# Adafruit_CLUE_nRF52840_Express.net
KiCad netlist of a schematic drawn in EAGLE
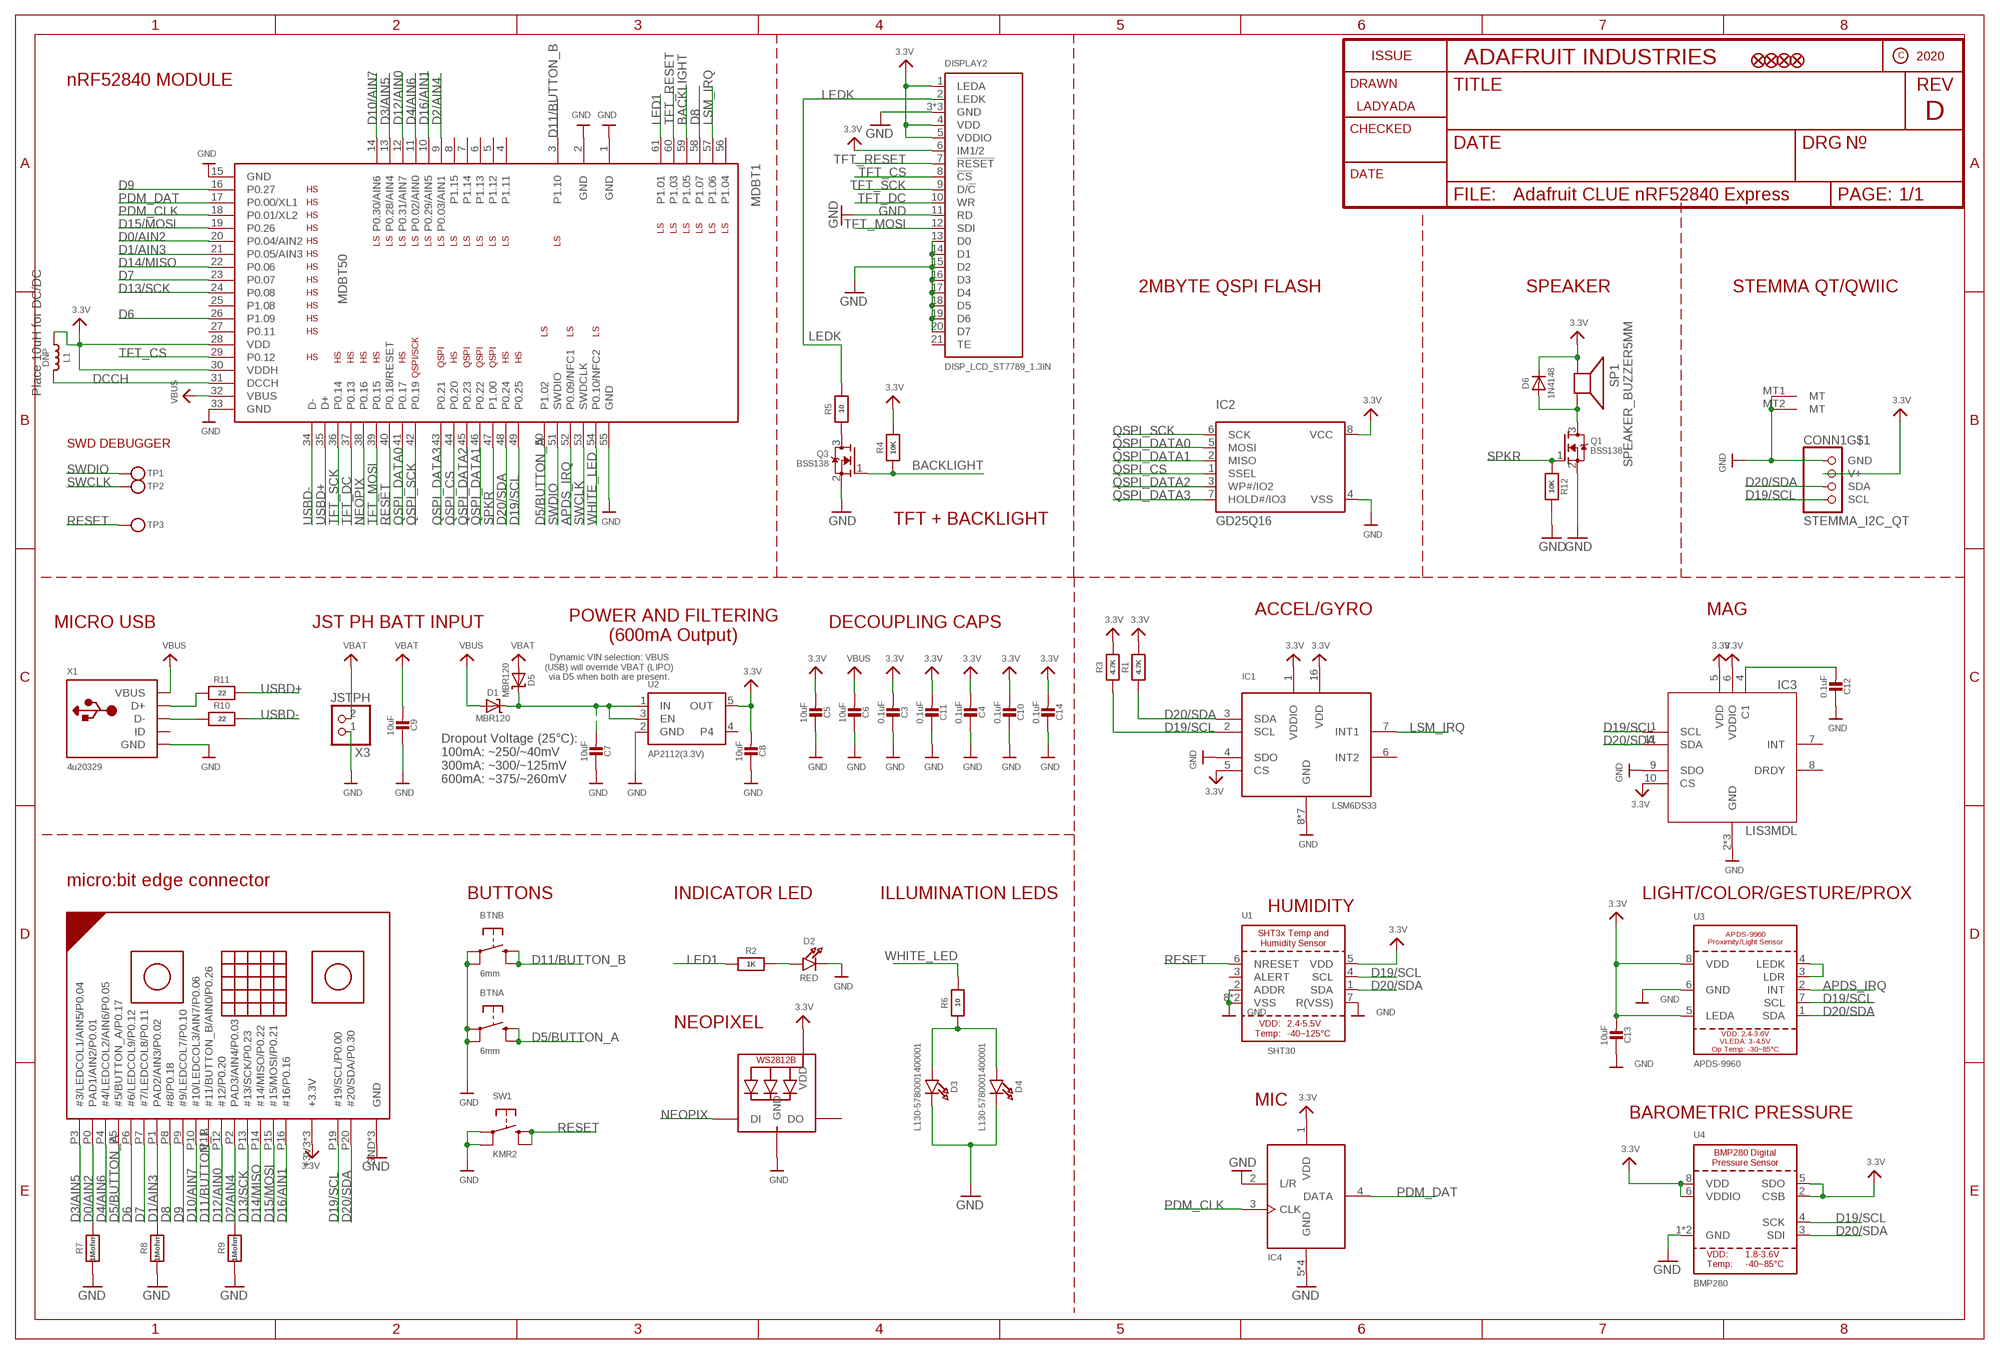
[diagram p0: schematic, sheet 1]

(export (version "E")
  (design (tool "Eeschema 10.0.6"))
  (components
    (comp (ref "BTNA")
      (value "6mm")
      (footprint "eagle-import:6MMX6MM_TACTILE_SMT")
      (libsource (lib "eagle-import") (part "SWITCH_TACT_SMT_6MM"))
    )
    (comp (ref "BTNB")
      (value "6mm")
      (footprint "eagle-import:6MMX6MM_TACTILE_SMT")
      (libsource (lib "eagle-import") (part "SWITCH_TACT_SMT_6MM"))
    )
    (comp (ref "C3")
      (value "0.1uF")
      (footprint "eagle-import:0603-NO")
      (libsource (lib "eagle-import") (part "CAP_CERAMIC0603_NO"))
    )
    (comp (ref "C4")
      (value "0.1uF")
      (footprint "eagle-import:0603-NO")
      (libsource (lib "eagle-import") (part "CAP_CERAMIC0603_NO"))
    )
    (comp (ref "C5")
      (value "10uF")
      (footprint "eagle-import:0805-NO")
      (libsource (lib "eagle-import") (part "CAP_CERAMIC0805-NOOUTLINE"))
    )
    (comp (ref "C6")
      (value "10uF")
      (footprint "eagle-import:0805-NO")
      (libsource (lib "eagle-import") (part "CAP_CERAMIC0805-NOOUTLINE"))
    )
    (comp (ref "C7")
      (value "10uF")
      (footprint "eagle-import:0805-NO")
      (libsource (lib "eagle-import") (part "CAP_CERAMIC0805-NOOUTLINE"))
    )
    (comp (ref "C8")
      (value "10uF")
      (footprint "eagle-import:0805-NO")
      (libsource (lib "eagle-import") (part "CAP_CERAMIC0805-NOOUTLINE"))
    )
    (comp (ref "C9")
      (value "10uF")
      (footprint "eagle-import:0805-NO")
      (libsource (lib "eagle-import") (part "CAP_CERAMIC0805-NOOUTLINE"))
    )
    (comp (ref "C10")
      (value "0.1uF")
      (footprint "eagle-import:0603-NO")
      (libsource (lib "eagle-import") (part "CAP_CERAMIC0603_NO"))
    )
    (comp (ref "C11")
      (value "0.1uF")
      (footprint "eagle-import:0603-NO")
      (libsource (lib "eagle-import") (part "CAP_CERAMIC0603_NO"))
    )
    (comp (ref "C12")
      (value "0.1uF")
      (footprint "eagle-import:0603-NO")
      (libsource (lib "eagle-import") (part "CAP_CERAMIC0603_NO"))
    )
    (comp (ref "C13")
      (value "10uF")
      (footprint "eagle-import:0805-NO")
      (libsource (lib "eagle-import") (part "CAP_CERAMIC0805-NOOUTLINE"))
    )
    (comp (ref "C14")
      (value "0.1uF")
      (footprint "eagle-import:0603-NO")
      (libsource (lib "eagle-import") (part "CAP_CERAMIC0603_NO"))
    )
    (comp (ref "CONN1")
      (value "STEMMA_I2C_QT")
      (footprint "eagle-import:JST_SH4")
      (libsource (lib "eagle-import") (part "STEMMA_I2C_QT"))
    )
    (comp (ref "D1")
      (value "MBR120")
      (footprint "eagle-import:SOD-123")
      (libsource (lib "eagle-import") (part "DIODE-SCHOTTKYSOD-123"))
    )
    (comp (ref "D2")
      (value "RED")
      (footprint "eagle-import:CHIPLED_0603_NOOUTLINE")
      (libsource (lib "eagle-import") (part "LED0603_NOOUTLINE"))
    )
    (comp (ref "D3")
      (value "L130-5780001400001")
      (footprint "eagle-import:EVERLIGHT_45-21")
      (libsource (lib "eagle-import") (part "LEDEV45-21"))
    )
    (comp (ref "D4")
      (value "L130-5780001400001")
      (footprint "eagle-import:EVERLIGHT_45-21")
      (libsource (lib "eagle-import") (part "LEDEV45-21"))
    )
    (comp (ref "D5")
      (value "MBR120")
      (footprint "eagle-import:SOD-123")
      (libsource (lib "eagle-import") (part "DIODE-SCHOTTKYSOD-123"))
    )
    (comp (ref "D6")
      (value "1N4148")
      (footprint "eagle-import:SOD-323")
      (libsource (lib "eagle-import") (part "DIODESOD-323"))
    )
    (comp (ref "DISPLAY2")
      (value "DISP_LCD_ST7789_1.3IN")
      (footprint "eagle-import:TFT_1.3IN_240X240_24P")
      (libsource (lib "eagle-import") (part "DISP_LCD_ST7789_1.3IN"))
    )
    (comp (ref "FID1")
      (value "FIDUCIAL_1MM")
      (footprint "eagle-import:FIDUCIAL_1MM")
      (libsource (lib "eagle-import") (part "FIDUCIAL_1MM"))
    )
    (comp (ref "FID2")
      (value "FIDUCIAL_1MM")
      (footprint "eagle-import:FIDUCIAL_1MM")
      (libsource (lib "eagle-import") (part "FIDUCIAL_1MM"))
    )
    (comp (ref "FID3")
      (value "FIDUCIAL_1MM")
      (footprint "eagle-import:FIDUCIAL_1MM")
      (libsource (lib "eagle-import") (part "FIDUCIAL_1MM"))
    )
    (comp (ref "FID4")
      (value "FIDUCIAL_1MM")
      (footprint "eagle-import:FIDUCIAL_1MM")
      (libsource (lib "eagle-import") (part "FIDUCIAL_1MM"))
    )
    (comp (ref "IC1")
      (value "LSM6DS33")
      (footprint "eagle-import:LGA16_3X3MM")
      (libsource (lib "eagle-import") (part "LSM6DS33"))
    )
    (comp (ref "IC2")
      (value "GD25Q16")
      (footprint "eagle-import:SOIC8_150MIL")
      (libsource (lib "eagle-import") (part "SPIFLASH_8PIN"))
    )
    (comp (ref "IC3")
      (value "LIS3MDL")
      (footprint "eagle-import:LGA12_2X2MM")
      (libsource (lib "eagle-import") (part "LIS3MDL"))
    )
    (comp (ref "IC4")
      (value "MIC_PDM")
      (footprint "eagle-import:SPK0415HM4H")
      (libsource (lib "eagle-import") (part "MIC_PDM_SPK0415"))
    )
    (comp (ref "L1")
      (value "DNP")
      (footprint "eagle-import:_0805MP")
      (libsource (lib "eagle-import") (part "INDUCTOR_0805MP"))
    )
    (comp (ref "LED1")
      (value "WS2812B3535")
      (footprint "eagle-import:LED3535")
      (libsource (lib "eagle-import") (part "WS2812B3535"))
    )
    (comp (ref "MB1")
      (value "MICRO:BIT_EDGE")
      (footprint "eagle-import:MICROBIT_EDGE")
      (libsource (lib "eagle-import") (part "MICRO{colon}BIT_EDGE"))
    )
    (comp (ref "MDBT1")
      (value "MDBT50")
      (footprint "eagle-import:MDBT50")
      (libsource (lib "eagle-import") (part "MDBT50"))
    )
    (comp (ref "Q1")
      (value "BSS138")
      (footprint "eagle-import:SOT23-WIDE")
      (libsource (lib "eagle-import") (part "MOSFET-NWIDE"))
    )
    (comp (ref "Q3")
      (value "BSS138")
      (footprint "eagle-import:SOT23-WIDE")
      (libsource (lib "eagle-import") (part "MOSFET-NWIDE"))
    )
    (comp (ref "R1")
      (value "4.7K")
      (footprint "eagle-import:0603-NO")
      (libsource (lib "eagle-import") (part "RESISTOR_0603_NOOUT"))
    )
    (comp (ref "R2")
      (value "1K")
      (footprint "eagle-import:0603-NO")
      (libsource (lib "eagle-import") (part "RESISTOR_0603_NOOUT"))
    )
    (comp (ref "R3")
      (value "4.7K")
      (footprint "eagle-import:0603-NO")
      (libsource (lib "eagle-import") (part "RESISTOR_0603_NOOUT"))
    )
    (comp (ref "R4")
      (value "10K")
      (footprint "eagle-import:0603-NO")
      (libsource (lib "eagle-import") (part "RESISTOR_0603_NOOUT"))
    )
    (comp (ref "R5")
      (value "10")
      (footprint "eagle-import:0603-NO")
      (libsource (lib "eagle-import") (part "RESISTOR_0603_NOOUT"))
    )
    (comp (ref "R6")
      (value "10")
      (footprint "eagle-import:0603-NO")
      (libsource (lib "eagle-import") (part "RESISTOR_0603_NOOUT"))
    )
    (comp (ref "R7")
      (value "1Mohm")
      (footprint "eagle-import:0603-NO")
      (libsource (lib "eagle-import") (part "RESISTOR_0603_NOOUT"))
    )
    (comp (ref "R8")
      (value "1Mohm")
      (footprint "eagle-import:0603-NO")
      (libsource (lib "eagle-import") (part "RESISTOR_0603_NOOUT"))
    )
    (comp (ref "R9")
      (value "1Mohm")
      (footprint "eagle-import:0603-NO")
      (libsource (lib "eagle-import") (part "RESISTOR_0603_NOOUT"))
    )
    (comp (ref "R10")
      (value "22")
      (footprint "eagle-import:0603-NO")
      (libsource (lib "eagle-import") (part "RESISTOR_0603_NOOUT"))
    )
    (comp (ref "R11")
      (value "22")
      (footprint "eagle-import:0603-NO")
      (libsource (lib "eagle-import") (part "RESISTOR_0603_NOOUT"))
    )
    (comp (ref "R12")
      (value "10K")
      (footprint "eagle-import:0603-NO")
      (libsource (lib "eagle-import") (part "RESISTOR_0603_NOOUT"))
    )
    (comp (ref "SP1")
      (value "SPEAKER_BUZZER5MM")
      (footprint "eagle-import:BUZZER_SMT_5MM")
      (libsource (lib "eagle-import") (part "SPEAKER_BUZZER5MM"))
    )
    (comp (ref "SW1")
      (value "KMR2")
      (footprint "eagle-import:EVQ-Q2_SMALLER")
      (libsource (lib "eagle-import") (part "SWITCH_TACT_SMT_EVQQ2_SMALL"))
    )
    (comp (ref "TP1")
      (value "TESTPOINTROUND1.5MM")
      (footprint "eagle-import:TESTPOINT_ROUND_1.5MM")
      (libsource (lib "eagle-import") (part "TESTPOINTROUND1.5MM"))
    )
    (comp (ref "TP2")
      (value "TESTPOINTROUND1.5MM")
      (footprint "eagle-import:TESTPOINT_ROUND_1.5MM")
      (libsource (lib "eagle-import") (part "TESTPOINTROUND1.5MM"))
    )
    (comp (ref "TP3")
      (value "TESTPOINTROUND1.5MM")
      (footprint "eagle-import:TESTPOINT_ROUND_1.5MM")
      (libsource (lib "eagle-import") (part "TESTPOINTROUND1.5MM"))
    )
    (comp (ref "U1")
      (value "SHT30")
      (footprint "eagle-import:SHT3X")
      (libsource (lib "eagle-import") (part "SHT3X"))
    )
    (comp (ref "U2")
      (value "AP2112(3.3V)")
      (footprint "eagle-import:SOT23-5")
      (libsource (lib "eagle-import") (part "VREG_SOT23-5"))
    )
    (comp (ref "U3")
      (value "APDS-9960")
      (footprint "eagle-import:APDS-9960")
      (libsource (lib "eagle-import") (part "APDS-9960"))
    )
    (comp (ref "U4")
      (value "BMP280")
      (footprint "eagle-import:BMP280")
      (libsource (lib "eagle-import") (part "BMP280"))
    )
    (comp (ref "X1")
      (value "4u20329")
      (footprint "eagle-import:4UCONN_20329_SLIM")
      (libsource (lib "eagle-import") (part "USB_SLIM"))
    )
    (comp (ref "X3")
      (value "JSTPH")
      (footprint "eagle-import:JSTPH2")
      (libsource (lib "eagle-import") (part "CON_JST_PH_2PIN"))
    )
  )
  (nets
    (net (code "1") (name "/APDS_IRQ") (class "Default")
      (node (ref "MDBT1") (pin "52") (pinfunction "P0.09/NFC1_52") (pintype "bidirectional"))
      (node (ref "U3") (pin "2") (pinfunction "INT_2") (pintype "output"))
    )
    (net (code "2") (name "/BACKLIGHT") (class "Default")
      (node (ref "MDBT1") (pin "59") (pinfunction "P1.05_59") (pintype "bidirectional"))
      (node (ref "Q3") (pin "1") (pinfunction "G_1") (pintype "bidirectional"))
      (node (ref "R4") (pin "1") (pinfunction "1_1") (pintype "passive"))
    )
    (net (code "3") (name "/D0{slash}AIN2") (class "Default")
      (node (ref "MB1") (pin "P0") (pinfunction "PAD1/AIN2/P0.01_P0") (pintype "bidirectional"))
      (node (ref "MDBT1") (pin "20") (pinfunction "P0.04/AIN2_20") (pintype "bidirectional"))
      (node (ref "R7") (pin "2") (pinfunction "2_2") (pintype "passive"))
    )
    (net (code "4") (name "/D1{slash}AIN3") (class "Default")
      (node (ref "MB1") (pin "P1") (pinfunction "PAD2/AIN3/P0.02_P1") (pintype "bidirectional"))
      (node (ref "MDBT1") (pin "21") (pinfunction "P0.05/AIN3_21") (pintype "bidirectional"))
      (node (ref "R8") (pin "2") (pinfunction "2_2") (pintype "passive"))
    )
    (net (code "5") (name "/D2{slash}AIN4") (class "Default")
      (node (ref "MB1") (pin "P2") (pinfunction "PAD3/AIN4/P0.03_P2") (pintype "bidirectional"))
      (node (ref "MDBT1") (pin "9") (pinfunction "P0.03/AIN1_9") (pintype "bidirectional"))
      (node (ref "R9") (pin "2") (pinfunction "2_2") (pintype "passive"))
    )
    (net (code "6") (name "/D3{slash}AIN5") (class "Default")
      (node (ref "MB1") (pin "P3") (pinfunction "#3/LEDCOL1/AIN5/P0.04_P3") (pintype "bidirectional"))
      (node (ref "MDBT1") (pin "13") (pinfunction "P0.28/AIN4_13") (pintype "bidirectional"))
    )
    (net (code "7") (name "/D4{slash}AIN6") (class "Default")
      (node (ref "MB1") (pin "P4") (pinfunction "#4/LEDCOL2/AIN6/P0.05_P4") (pintype "bidirectional"))
      (node (ref "MDBT1") (pin "11") (pinfunction "P0.02/AIN0_11") (pintype "bidirectional"))
    )
    (net (code "8") (name "/D5{slash}BUTTON_A") (class "Default")
      (node (ref "BTNA") (pin "B") (pinfunction "S_B") (pintype "passive"))
      (node (ref "BTNA") (pin "B'") (pinfunction "S1_B'") (pintype "passive"))
      (node (ref "MB1") (pin "P5") (pinfunction "#5/BUTTON_A/P0.17_P5") (pintype "bidirectional"))
      (node (ref "MDBT1") (pin "50") (pinfunction "P1.02_50") (pintype "bidirectional"))
    )
    (net (code "9") (name "/D6") (class "Default")
      (node (ref "MB1") (pin "P6") (pinfunction "#6/LEDCOL9/P0.12_P6") (pintype "bidirectional"))
      (node (ref "MDBT1") (pin "26") (pinfunction "P1.09_26") (pintype "bidirectional"))
    )
    (net (code "10") (name "/D7") (class "Default")
      (node (ref "MB1") (pin "P7") (pinfunction "#7/LEDCOL8/P0.11_P7") (pintype "bidirectional"))
      (node (ref "MDBT1") (pin "23") (pinfunction "P0.07_23") (pintype "bidirectional"))
    )
    (net (code "11") (name "/D8") (class "Default")
      (node (ref "MB1") (pin "P8") (pinfunction "#8/P0.18_P8") (pintype "bidirectional"))
      (node (ref "MDBT1") (pin "58") (pinfunction "P1.07_58") (pintype "bidirectional"))
    )
    (net (code "12") (name "/D9") (class "Default")
      (node (ref "MB1") (pin "P9") (pinfunction "#9/LEDCOL7/P0.10_P9") (pintype "bidirectional"))
      (node (ref "MDBT1") (pin "16") (pinfunction "P0.27_16") (pintype "bidirectional"))
    )
    (net (code "13") (name "/D10{slash}AIN7") (class "Default")
      (node (ref "MB1") (pin "P10") (pinfunction "#10/LEDCOL3/AIN7/P0.06_P10") (pintype "bidirectional"))
      (node (ref "MDBT1") (pin "14") (pinfunction "P0.30/AIN6_14") (pintype "bidirectional"))
    )
    (net (code "14") (name "/D11{slash}BUTTON_B") (class "Default")
      (node (ref "BTNB") (pin "B") (pinfunction "S_B") (pintype "passive"))
      (node (ref "BTNB") (pin "B'") (pinfunction "S1_B'") (pintype "passive"))
      (node (ref "MB1") (pin "P11") (pinfunction "#11/BUTTON_B/AIN0/P0.26_P11") (pintype "bidirectional"))
      (node (ref "MDBT1") (pin "3") (pinfunction "P1.10_3") (pintype "bidirectional"))
    )
    (net (code "15") (name "/D12{slash}AIN0") (class "Default")
      (node (ref "MB1") (pin "P12") (pinfunction "#12/P0.20_P12") (pintype "bidirectional"))
      (node (ref "MDBT1") (pin "12") (pinfunction "P0.31/AIN7_12") (pintype "bidirectional"))
    )
    (net (code "16") (name "/D13{slash}SCK") (class "Default")
      (node (ref "MB1") (pin "P13") (pinfunction "#13/SCK/P0.23_P13") (pintype "bidirectional"))
      (node (ref "MDBT1") (pin "24") (pinfunction "P0.08_24") (pintype "bidirectional"))
    )
    (net (code "17") (name "/D14{slash}MISO") (class "Default")
      (node (ref "MB1") (pin "P14") (pinfunction "#14/MISO/P0.22_P14") (pintype "bidirectional"))
      (node (ref "MDBT1") (pin "22") (pinfunction "P0.06_22") (pintype "bidirectional"))
    )
    (net (code "18") (name "/D15{slash}MOSI") (class "Default")
      (node (ref "MB1") (pin "P15") (pinfunction "#15/MOSI/P0.21_P15") (pintype "bidirectional"))
      (node (ref "MDBT1") (pin "19") (pinfunction "P0.26_19") (pintype "bidirectional"))
    )
    (net (code "19") (name "/D16{slash}AIN1") (class "Default")
      (node (ref "MB1") (pin "P16") (pinfunction "#16/P0.16_P16") (pintype "bidirectional"))
      (node (ref "MDBT1") (pin "10") (pinfunction "P0.29/AIN5_10") (pintype "bidirectional"))
    )
    (net (code "20") (name "/D19{slash}SCL") (class "Default")
      (node (ref "CONN1") (pin "4") (pinfunction "SCL_4") (pintype "passive"))
      (node (ref "IC1") (pin "2") (pinfunction "SCL_2") (pintype "bidirectional"))
      (node (ref "IC3") (pin "1") (pinfunction "SCL_1") (pintype "input"))
      (node (ref "MB1") (pin "P19") (pinfunction "#19/SCL/P0.00_P19") (pintype "bidirectional"))
      (node (ref "MDBT1") (pin "49") (pinfunction "P0.25_49") (pintype "bidirectional"))
      (node (ref "R3") (pin "1") (pinfunction "1_1") (pintype "passive"))
      (node (ref "U1") (pin "4") (pinfunction "SCL_4") (pintype "bidirectional"))
      (node (ref "U3") (pin "7") (pinfunction "SCL_7") (pintype "input"))
      (node (ref "U4") (pin "4") (pinfunction "SCK_4") (pintype "input"))
    )
    (net (code "21") (name "/D20{slash}SDA") (class "Default")
      (node (ref "CONN1") (pin "3") (pinfunction "SDA_3") (pintype "passive"))
      (node (ref "IC1") (pin "3") (pinfunction "SDA_3") (pintype "bidirectional"))
      (node (ref "IC3") (pin "11") (pinfunction "SDA_11") (pintype "bidirectional"))
      (node (ref "MB1") (pin "P20") (pinfunction "#20/SDA/P0.30_P20") (pintype "bidirectional"))
      (node (ref "MDBT1") (pin "48") (pinfunction "P0.24_48") (pintype "bidirectional"))
      (node (ref "R1") (pin "1") (pinfunction "1_1") (pintype "passive"))
      (node (ref "U1") (pin "1") (pinfunction "SDA_1") (pintype "bidirectional"))
      (node (ref "U3") (pin "1") (pinfunction "SDA_1") (pintype "bidirectional"))
      (node (ref "U4") (pin "3") (pinfunction "SDI_3") (pintype "input"))
    )
    (net (code "22") (name "/DCCH") (class "Default")
      (node (ref "L1") (pin "2") (pinfunction "2_2") (pintype "passive"))
      (node (ref "MDBT1") (pin "31") (pinfunction "DCCH_31") (pintype "bidirectional"))
    )
    (net (code "23") (name "/LED1") (class "Default")
      (node (ref "MDBT1") (pin "61") (pinfunction "P1.01_61") (pintype "bidirectional"))
      (node (ref "R2") (pin "1") (pinfunction "1_1") (pintype "passive"))
    )
    (net (code "24") (name "/LEDK") (class "Default")
      (node (ref "DISPLAY2") (pin "2") (pinfunction "LEDK_2") (pintype "input"))
      (node (ref "R5") (pin "2") (pinfunction "2_2") (pintype "passive"))
    )
    (net (code "25") (name "/LSM_IRQ") (class "Default")
      (node (ref "IC1") (pin "7") (pinfunction "INT1_7") (pintype "output"))
      (node (ref "MDBT1") (pin "57") (pinfunction "P1.06_57") (pintype "bidirectional"))
    )
    (net (code "26") (name "/NEOPIX") (class "Default")
      (node (ref "LED1") (pin "1") (pinfunction "DI_1") (pintype "input"))
      (node (ref "MDBT1") (pin "38") (pinfunction "P0.16_38") (pintype "bidirectional"))
    )
    (net (code "27") (name "/PDM_CLK") (class "Default")
      (node (ref "IC4") (pin "3") (pinfunction "CLK_3") (pintype "input"))
      (node (ref "MDBT1") (pin "18") (pinfunction "P0.01/XL2_18") (pintype "bidirectional"))
    )
    (net (code "28") (name "/PDM_DAT") (class "Default")
      (node (ref "IC4") (pin "4") (pinfunction "DATA_4") (pintype "bidirectional"))
      (node (ref "MDBT1") (pin "17") (pinfunction "P0.00/XL1_17") (pintype "bidirectional"))
    )
    (net (code "29") (name "/QSPI_CS") (class "Default")
      (node (ref "IC2") (pin "1") (pinfunction "SSEL_1") (pintype "bidirectional"))
      (node (ref "MDBT1") (pin "44") (pinfunction "P0.20_44") (pintype "bidirectional"))
    )
    (net (code "30") (name "/QSPI_DATA0") (class "Default")
      (node (ref "IC2") (pin "5") (pinfunction "MOSI_5") (pintype "bidirectional"))
      (node (ref "MDBT1") (pin "41") (pinfunction "P0.17_41") (pintype "bidirectional"))
    )
    (net (code "31") (name "/QSPI_DATA1") (class "Default")
      (node (ref "IC2") (pin "2") (pinfunction "MISO_2") (pintype "bidirectional"))
      (node (ref "MDBT1") (pin "46") (pinfunction "P0.22_46") (pintype "bidirectional"))
    )
    (net (code "32") (name "/QSPI_DATA2") (class "Default")
      (node (ref "IC2") (pin "3") (pinfunction "WP#/IO2_3") (pintype "bidirectional"))
      (node (ref "MDBT1") (pin "45") (pinfunction "P0.23_45") (pintype "bidirectional"))
    )
    (net (code "33") (name "/QSPI_DATA3") (class "Default")
      (node (ref "IC2") (pin "7") (pinfunction "HOLD#/IO3_7") (pintype "bidirectional"))
      (node (ref "MDBT1") (pin "43") (pinfunction "P0.21_43") (pintype "bidirectional"))
    )
    (net (code "34") (name "/QSPI_SCK") (class "Default")
      (node (ref "IC2") (pin "6") (pinfunction "SCK_6") (pintype "bidirectional"))
      (node (ref "MDBT1") (pin "42") (pinfunction "P0.19_42") (pintype "bidirectional"))
    )
    (net (code "35") (name "/RESET") (class "Default")
      (node (ref "MDBT1") (pin "40") (pinfunction "P0.18/RESET_40") (pintype "bidirectional"))
      (node (ref "SW1") (pin "B") (pinfunction "S_B") (pintype "passive"))
      (node (ref "SW1") (pin "B'") (pinfunction "S1_B'") (pintype "passive"))
      (node (ref "TP3") (pin "P$1") (pinfunction "P$1_P$1") (pintype "bidirectional"))
      (node (ref "U1") (pin "6") (pinfunction "NRESET_6") (pintype "bidirectional"))
    )
    (net (code "36") (name "/SPKR") (class "Default")
      (node (ref "MDBT1") (pin "47") (pinfunction "P1.00_47") (pintype "bidirectional"))
      (node (ref "Q1") (pin "1") (pinfunction "G_1") (pintype "bidirectional"))
      (node (ref "R12") (pin "1") (pinfunction "1_1") (pintype "passive"))
    )
    (net (code "37") (name "/SWCLK") (class "Default")
      (node (ref "MDBT1") (pin "53") (pinfunction "SWDCLK_53") (pintype "bidirectional"))
      (node (ref "TP2") (pin "P$1") (pinfunction "P$1_P$1") (pintype "bidirectional"))
    )
    (net (code "38") (name "/SWDIO") (class "Default")
      (node (ref "MDBT1") (pin "51") (pinfunction "SWDIO_51") (pintype "bidirectional"))
      (node (ref "TP1") (pin "P$1") (pinfunction "P$1_P$1") (pintype "bidirectional"))
    )
    (net (code "39") (name "/TFT_CS") (class "Default")
      (node (ref "DISPLAY2") (pin "8") (pinfunction "~{CS}_8") (pintype "input"))
      (node (ref "MDBT1") (pin "29") (pinfunction "P0.12_29") (pintype "bidirectional"))
    )
    (net (code "40") (name "/TFT_DC") (class "Default")
      (node (ref "DISPLAY2") (pin "10") (pinfunction "WR_10") (pintype "input"))
      (node (ref "MDBT1") (pin "37") (pinfunction "P0.13_37") (pintype "bidirectional"))
    )
    (net (code "41") (name "/TFT_MOSI") (class "Default")
      (node (ref "DISPLAY2") (pin "12") (pinfunction "SDI_12") (pintype "input"))
      (node (ref "MDBT1") (pin "39") (pinfunction "P0.15_39") (pintype "bidirectional"))
    )
    (net (code "42") (name "/TFT_RESET") (class "Default")
      (node (ref "DISPLAY2") (pin "7") (pinfunction "~{RESET}_7") (pintype "input"))
      (node (ref "MDBT1") (pin "60") (pinfunction "P1.03_60") (pintype "bidirectional"))
    )
    (net (code "43") (name "/TFT_SCK") (class "Default")
      (node (ref "DISPLAY2") (pin "9") (pinfunction "D/~{C}_9") (pintype "input"))
      (node (ref "MDBT1") (pin "36") (pinfunction "P0.14_36") (pintype "bidirectional"))
    )
    (net (code "44") (name "/USBD+") (class "Default")
      (node (ref "MDBT1") (pin "35") (pinfunction "D+_35") (pintype "bidirectional"))
      (node (ref "R11") (pin "2") (pinfunction "2_2") (pintype "passive"))
    )
    (net (code "45") (name "/USBD-") (class "Default")
      (node (ref "MDBT1") (pin "34") (pinfunction "D-_34") (pintype "bidirectional"))
      (node (ref "R10") (pin "2") (pinfunction "2_2") (pintype "passive"))
    )
    (net (code "46") (name "/WHITE_LED") (class "Default")
      (node (ref "MDBT1") (pin "54") (pinfunction "P0.10/NFC2_54") (pintype "bidirectional"))
      (node (ref "R6") (pin "2") (pinfunction "2_2") (pintype "passive"))
    )
    (net (code "47") (name "3.3V") (class "Default")
      (node (ref "C10") (pin "2") (pinfunction "2_2") (pintype "passive"))
      (node (ref "C11") (pin "2") (pinfunction "2_2") (pintype "passive"))
      (node (ref "C13") (pin "2") (pinfunction "2_2") (pintype "passive"))
      (node (ref "C14") (pin "2") (pinfunction "2_2") (pintype "passive"))
      (node (ref "C3") (pin "2") (pinfunction "2_2") (pintype "passive"))
      (node (ref "C4") (pin "2") (pinfunction "2_2") (pintype "passive"))
      (node (ref "C5") (pin "2") (pinfunction "2_2") (pintype "passive"))
      (node (ref "C8") (pin "2") (pinfunction "2_2") (pintype "passive"))
      (node (ref "CONN1") (pin "2") (pinfunction "V+_2") (pintype "passive"))
      (node (ref "D6") (pin "C") (pinfunction "C_C") (pintype "passive"))
      (node (ref "DISPLAY2") (pin "1") (pinfunction "LEDA_1") (pintype "input"))
      (node (ref "DISPLAY2") (pin "4") (pinfunction "VDD_4") (pintype "power_in"))
      (node (ref "DISPLAY2") (pin "5") (pinfunction "VDDIO_5") (pintype "power_in"))
      (node (ref "DISPLAY2") (pin "6") (pinfunction "IM1/2_6") (pintype "input"))
      (node (ref "IC1") (pin "1") (pinfunction "VDDIO_1") (pintype "power_in"))
      (node (ref "IC1") (pin "16") (pinfunction "VDD_16") (pintype "power_in"))
      (node (ref "IC1") (pin "5") (pinfunction "CS_5") (pintype "input"))
      (node (ref "IC2") (pin "8") (pinfunction "VCC_8") (pintype "bidirectional"))
      (node (ref "IC3") (pin "10") (pinfunction "CS_10") (pintype "input"))
      (node (ref "IC3") (pin "5") (pinfunction "VDD_5") (pintype "power_in"))
      (node (ref "IC3") (pin "6") (pinfunction "VDDIO_6") (pintype "power_in"))
      (node (ref "IC4") (pin "1") (pinfunction "VDD_1") (pintype "power_in"))
      (node (ref "L1") (pin "1") (pinfunction "1_1") (pintype "passive"))
      (node (ref "LED1") (pin "2") (pinfunction "VDD_2") (pintype "power_in"))
      (node (ref "MB1") (pin "+3V3") (pinfunction "+3.3V_+3V3") (pintype "power_in"))
      (node (ref "MB1") (pin "+3V3@1") (pinfunction "+3.3V_+3V3@1") (pintype "power_in"))
      (node (ref "MB1") (pin "+3V3@2") (pinfunction "+3.3V_+3V3@2") (pintype "power_in"))
      (node (ref "MDBT1") (pin "28") (pinfunction "VDD_28") (pintype "bidirectional"))
      (node (ref "MDBT1") (pin "30") (pinfunction "VDDH_30") (pintype "bidirectional"))
      (node (ref "R1") (pin "2") (pinfunction "2_2") (pintype "passive"))
      (node (ref "R3") (pin "2") (pinfunction "2_2") (pintype "passive"))
      (node (ref "R4") (pin "2") (pinfunction "2_2") (pintype "passive"))
      (node (ref "SP1") (pin "+") (pinfunction "+_+") (pintype "passive"))
      (node (ref "U1") (pin "5") (pinfunction "VDD_5") (pintype "power_in"))
      (node (ref "U2") (pin "5") (pinfunction "OUT_5") (pintype "power_in"))
      (node (ref "U3") (pin "5") (pinfunction "LEDA_5") (pintype "power_in"))
      (node (ref "U3") (pin "8") (pinfunction "VDD_8") (pintype "power_in"))
      (node (ref "U4") (pin "2") (pinfunction "CSB_2") (pintype "input"))
      (node (ref "U4") (pin "5") (pinfunction "SDO_5") (pintype "output"))
      (node (ref "U4") (pin "6") (pinfunction "VDDIO_6") (pintype "power_in"))
      (node (ref "U4") (pin "8") (pinfunction "VDD_8") (pintype "power_in"))
    )
    (net (code "48") (name "GND") (class "Default")
      (node (ref "BTNA") (pin "A") (pinfunction "P_A") (pintype "passive"))
      (node (ref "BTNA") (pin "A'") (pinfunction "P1_A'") (pintype "passive"))
      (node (ref "BTNB") (pin "A") (pinfunction "P_A") (pintype "passive"))
      (node (ref "BTNB") (pin "A'") (pinfunction "P1_A'") (pintype "passive"))
      (node (ref "C10") (pin "1") (pinfunction "1_1") (pintype "passive"))
      (node (ref "C11") (pin "1") (pinfunction "1_1") (pintype "passive"))
      (node (ref "C12") (pin "1") (pinfunction "1_1") (pintype "passive"))
      (node (ref "C13") (pin "1") (pinfunction "1_1") (pintype "passive"))
      (node (ref "C14") (pin "1") (pinfunction "1_1") (pintype "passive"))
      (node (ref "C3") (pin "1") (pinfunction "1_1") (pintype "passive"))
      (node (ref "C4") (pin "1") (pinfunction "1_1") (pintype "passive"))
      (node (ref "C5") (pin "1") (pinfunction "1_1") (pintype "passive"))
      (node (ref "C6") (pin "1") (pinfunction "1_1") (pintype "passive"))
      (node (ref "C7") (pin "1") (pinfunction "1_1") (pintype "passive"))
      (node (ref "C8") (pin "1") (pinfunction "1_1") (pintype "passive"))
      (node (ref "C9") (pin "1") (pinfunction "1_1") (pintype "passive"))
      (node (ref "CONN1") (pin "1") (pinfunction "GND_1") (pintype "passive"))
      (node (ref "CONN1") (pin "MT1") (pinfunction "MT_MT1") (pintype "bidirectional"))
      (node (ref "CONN1") (pin "MT2") (pinfunction "MT_MT2") (pintype "bidirectional"))
      (node (ref "D2") (pin "C") (pinfunction "C_C") (pintype "passive"))
      (node (ref "D3") (pin "K") (pinfunction "C_K") (pintype "passive"))
      (node (ref "D4") (pin "K") (pinfunction "C_K") (pintype "passive"))
      (node (ref "DISPLAY2") (pin "11") (pinfunction "RD_11") (pintype "input"))
      (node (ref "DISPLAY2") (pin "13") (pinfunction "D0_13") (pintype "bidirectional"))
      (node (ref "DISPLAY2") (pin "14") (pinfunction "D1_14") (pintype "bidirectional"))
      (node (ref "DISPLAY2") (pin "15") (pinfunction "D2_15") (pintype "bidirectional"))
      (node (ref "DISPLAY2") (pin "16") (pinfunction "D3_16") (pintype "bidirectional"))
      (node (ref "DISPLAY2") (pin "17") (pinfunction "D4_17") (pintype "bidirectional"))
      (node (ref "DISPLAY2") (pin "18") (pinfunction "D5_18") (pintype "bidirectional"))
      (node (ref "DISPLAY2") (pin "19") (pinfunction "D6_19") (pintype "bidirectional"))
      (node (ref "DISPLAY2") (pin "20") (pinfunction "D7_20") (pintype "bidirectional"))
      (node (ref "DISPLAY2") (pin "23") (pinfunction "GND_23") (pintype "power_in"))
      (node (ref "DISPLAY2") (pin "24") (pinfunction "GND_24") (pintype "power_in"))
      (node (ref "DISPLAY2") (pin "3") (pinfunction "GND_3") (pintype "power_in"))
      (node (ref "IC1") (pin "10") (pinfunction "GND_10") (pintype "power_in"))
      (node (ref "IC1") (pin "11") (pinfunction "GND_11") (pintype "power_in"))
      (node (ref "IC1") (pin "12") (pinfunction "GND_12") (pintype "power_in"))
      (node (ref "IC1") (pin "13") (pinfunction "GND_13") (pintype "power_in"))
      (node (ref "IC1") (pin "15") (pinfunction "GND_15") (pintype "power_in"))
      (node (ref "IC1") (pin "4") (pinfunction "SDO_4") (pintype "bidirectional"))
      (node (ref "IC1") (pin "8") (pinfunction "GND_8") (pintype "power_in"))
      (node (ref "IC1") (pin "9") (pinfunction "GND_9") (pintype "power_in"))
      (node (ref "IC2") (pin "4") (pinfunction "VSS_4") (pintype "bidirectional"))
      (node (ref "IC3") (pin "12") (pinfunction "GND_12") (pintype "power_in"))
      (node (ref "IC3") (pin "2") (pinfunction "GND_2") (pintype "power_in"))
      (node (ref "IC3") (pin "3") (pinfunction "GND_3") (pintype "power_in"))
      (node (ref "IC3") (pin "9") (pinfunction "SDO_9") (pintype "bidirectional"))
      (node (ref "IC4") (pin "2") (pinfunction "L/R_2") (pintype "input"))
      (node (ref "IC4") (pin "5") (pinfunction "GND_5") (pintype "power_in"))
      (node (ref "IC4") (pin "6") (pinfunction "GND_6") (pintype "power_in"))
      (node (ref "IC4") (pin "7") (pinfunction "GND_7") (pintype "power_in"))
      (node (ref "IC4") (pin "8") (pinfunction "GND_8") (pintype "power_in"))
      (node (ref "LED1") (pin "4") (pinfunction "GND_4") (pintype "power_in"))
      (node (ref "MB1") (pin "GND") (pinfunction "GND_GND") (pintype "power_in"))
      (node (ref "MB1") (pin "GND@1") (pinfunction "GND_GND@1") (pintype "power_in"))
      (node (ref "MB1") (pin "GND@2") (pinfunction "GND_GND@2") (pintype "power_in"))
      (node (ref "MDBT1") (pin "1") (pinfunction "GND_1") (pintype "bidirectional"))
      (node (ref "MDBT1") (pin "15") (pinfunction "GND_15") (pintype "bidirectional"))
      (node (ref "MDBT1") (pin "2") (pinfunction "GND_2") (pintype "bidirectional"))
      (node (ref "MDBT1") (pin "33") (pinfunction "GND_33") (pintype "bidirectional"))
      (node (ref "MDBT1") (pin "55") (pinfunction "GND_55") (pintype "bidirectional"))
      (node (ref "Q1") (pin "2") (pinfunction "S_2") (pintype "bidirectional"))
      (node (ref "Q3") (pin "2") (pinfunction "S_2") (pintype "bidirectional"))
      (node (ref "R12") (pin "2") (pinfunction "2_2") (pintype "passive"))
      (node (ref "R7") (pin "1") (pinfunction "1_1") (pintype "passive"))
      (node (ref "R8") (pin "1") (pinfunction "1_1") (pintype "passive"))
      (node (ref "R9") (pin "1") (pinfunction "1_1") (pintype "passive"))
      (node (ref "SW1") (pin "A") (pinfunction "P_A") (pintype "passive"))
      (node (ref "SW1") (pin "A'") (pinfunction "P1_A'") (pintype "passive"))
      (node (ref "U1") (pin "2") (pinfunction "ADDR_2") (pintype "bidirectional"))
      (node (ref "U1") (pin "7") (pinfunction "R(VSS)_7") (pintype "bidirectional"))
      (node (ref "U1") (pin "8") (pinfunction "VSS_8") (pintype "power_in"))
      (node (ref "U1") (pin "THERMAL") (pinfunction "VSS_THERMAL") (pintype "power_in"))
      (node (ref "U2") (pin "2") (pinfunction "GND_2") (pintype "power_in"))
      (node (ref "U3") (pin "6") (pinfunction "GND_6") (pintype "power_in"))
      (node (ref "U4") (pin "1") (pinfunction "GND_1") (pintype "power_in"))
      (node (ref "U4") (pin "7") (pinfunction "GND_7") (pintype "power_in"))
      (node (ref "X1") (pin "BASE@1") (pinfunction "GND_BASE@1") (pintype "power_in"))
      (node (ref "X1") (pin "BASE@2") (pinfunction "GND_BASE@2") (pintype "power_in"))
      (node (ref "X1") (pin "GND") (pinfunction "GND_GND") (pintype "power_in"))
      (node (ref "X1") (pin "SPRT@1") (pinfunction "GND_SPRT@1") (pintype "power_in"))
      (node (ref "X1") (pin "SPRT@2") (pinfunction "GND_SPRT@2") (pintype "power_in"))
      (node (ref "X1") (pin "SPRT@3") (pinfunction "GND_SPRT@3") (pintype "power_in"))
      (node (ref "X1") (pin "SPRT@4") (pinfunction "GND_SPRT@4") (pintype "power_in"))
      (node (ref "X3") (pin "1") (pinfunction "1_1") (pintype "passive"))
    )
    (net (code "49") (name "Net-(D2-PadA)") (class "Default")
      (node (ref "D2") (pin "A") (pinfunction "A_A") (pintype "passive"))
      (node (ref "R2") (pin "2") (pinfunction "2_2") (pintype "passive"))
    )
    (net (code "50") (name "Net-(D3-PadA)") (class "Default")
      (node (ref "D3") (pin "A") (pinfunction "A_A") (pintype "passive"))
      (node (ref "D4") (pin "A") (pinfunction "A_A") (pintype "passive"))
      (node (ref "R6") (pin "1") (pinfunction "1_1") (pintype "passive"))
    )
    (net (code "51") (name "Net-(IC3-C1)") (class "Default")
      (node (ref "C12") (pin "2") (pinfunction "2_2") (pintype "passive"))
      (node (ref "IC3") (pin "4") (pinfunction "C1_4") (pintype "input"))
    )
    (net (code "52") (name "Net-(Q1-D)") (class "Default")
      (node (ref "D6") (pin "A") (pinfunction "A_A") (pintype "passive"))
      (node (ref "Q1") (pin "3") (pinfunction "D_3") (pintype "bidirectional"))
      (node (ref "SP1") (pin "-") (pinfunction "-_-") (pintype "passive"))
    )
    (net (code "53") (name "Net-(Q3-D)") (class "Default")
      (node (ref "Q3") (pin "3") (pinfunction "D_3") (pintype "bidirectional"))
      (node (ref "R5") (pin "1") (pinfunction "1_1") (pintype "passive"))
    )
    (net (code "54") (name "Net-(R10-Pad1)") (class "Default")
      (node (ref "R10") (pin "1") (pinfunction "1_1") (pintype "passive"))
      (node (ref "X1") (pin "D-") (pinfunction "D-_D-") (pintype "bidirectional"))
    )
    (net (code "55") (name "Net-(R11-Pad1)") (class "Default")
      (node (ref "R11") (pin "1") (pinfunction "1_1") (pintype "passive"))
      (node (ref "X1") (pin "D+") (pinfunction "D+_D+") (pintype "bidirectional"))
    )
    (net (code "56") (name "Net-(U2-EN)") (class "Default")
      (node (ref "C7") (pin "2") (pinfunction "2_2") (pintype "passive"))
      (node (ref "D1") (pin "C") (pinfunction "C_C") (pintype "passive"))
      (node (ref "D5") (pin "C") (pinfunction "C_C") (pintype "passive"))
      (node (ref "U2") (pin "1") (pinfunction "IN_1") (pintype "power_in"))
      (node (ref "U2") (pin "3") (pinfunction "EN_3") (pintype "input"))
    )
    (net (code "57") (name "Net-(U3-LDR)") (class "Default")
      (node (ref "U3") (pin "3") (pinfunction "LDR_3") (pintype "bidirectional"))
      (node (ref "U3") (pin "4") (pinfunction "LEDK_4") (pintype "bidirectional"))
    )
    (net (code "58") (name "VBAT") (class "Default")
      (node (ref "C9") (pin "2") (pinfunction "2_2") (pintype "passive"))
      (node (ref "D5") (pin "A") (pinfunction "A_A") (pintype "passive"))
      (node (ref "X3") (pin "2") (pinfunction "2_2") (pintype "passive"))
    )
    (net (code "59") (name "VBUS") (class "Default")
      (node (ref "C6") (pin "2") (pinfunction "2_2") (pintype "passive"))
      (node (ref "D1") (pin "A") (pinfunction "A_A") (pintype "passive"))
      (node (ref "MDBT1") (pin "32") (pinfunction "VBUS_32") (pintype "bidirectional"))
      (node (ref "X1") (pin "VBUS") (pinfunction "VBUS_VBUS") (pintype "power_in"))
    )
    (net (code "60") (name "unconnected-(DISPLAY2-TE-Pad21)") (class "Default")
      (node (ref "DISPLAY2") (pin "21") (pinfunction "TE_21") (pintype "output"))
    )
    (net (code "61") (name "unconnected-(IC1-INT2-Pad6)") (class "Default")
      (node (ref "IC1") (pin "6") (pinfunction "INT2_6") (pintype "output"))
    )
    (net (code "62") (name "unconnected-(IC3-DRDY-Pad8)") (class "Default")
      (node (ref "IC3") (pin "8") (pinfunction "DRDY_8") (pintype "output"))
    )
    (net (code "63") (name "unconnected-(IC3-INT-Pad7)") (class "Default")
      (node (ref "IC3") (pin "7") (pinfunction "INT_7") (pintype "output"))
    )
    (net (code "64") (name "unconnected-(LED1-DO-Pad3)") (class "Default")
      (node (ref "LED1") (pin "3") (pinfunction "DO_3") (pintype "output"))
    )
    (net (code "65") (name "unconnected-(MDBT1-P0.11-Pad27)") (class "Default")
      (node (ref "MDBT1") (pin "27") (pinfunction "P0.11_27") (pintype "bidirectional"))
    )
    (net (code "66") (name "unconnected-(MDBT1-P1.04-Pad56)") (class "Default")
      (node (ref "MDBT1") (pin "56") (pinfunction "P1.04_56") (pintype "bidirectional"))
    )
    (net (code "67") (name "unconnected-(MDBT1-P1.08-Pad25)") (class "Default")
      (node (ref "MDBT1") (pin "25") (pinfunction "P1.08_25") (pintype "bidirectional"))
    )
    (net (code "68") (name "unconnected-(MDBT1-P1.11-Pad4)") (class "Default")
      (node (ref "MDBT1") (pin "4") (pinfunction "P1.11_4") (pintype "bidirectional"))
    )
    (net (code "69") (name "unconnected-(MDBT1-P1.12-Pad5)") (class "Default")
      (node (ref "MDBT1") (pin "5") (pinfunction "P1.12_5") (pintype "bidirectional"))
    )
    (net (code "70") (name "unconnected-(MDBT1-P1.13-Pad6)") (class "Default")
      (node (ref "MDBT1") (pin "6") (pinfunction "P1.13_6") (pintype "bidirectional"))
    )
    (net (code "71") (name "unconnected-(MDBT1-P1.14-Pad7)") (class "Default")
      (node (ref "MDBT1") (pin "7") (pinfunction "P1.14_7") (pintype "bidirectional"))
    )
    (net (code "72") (name "unconnected-(MDBT1-P1.15-Pad8)") (class "Default")
      (node (ref "MDBT1") (pin "8") (pinfunction "P1.15_8") (pintype "bidirectional"))
    )
    (net (code "73") (name "unconnected-(U1-ALERT-Pad3)") (class "Default")
      (node (ref "U1") (pin "3") (pinfunction "ALERT_3") (pintype "bidirectional"))
    )
    (net (code "74") (name "unconnected-(U2-P4-Pad4)") (class "Default")
      (node (ref "U2") (pin "4") (pinfunction "P4_4") (pintype "bidirectional"))
    )
    (net (code "75") (name "unconnected-(X1-PadID)") (class "Default")
      (node (ref "X1") (pin "ID") (pinfunction "ID_ID") (pintype "bidirectional"))
    )
  )
)
